# AD_605_Sheet1.net
KiCad netlist of a schematic drawn in Altium Designer
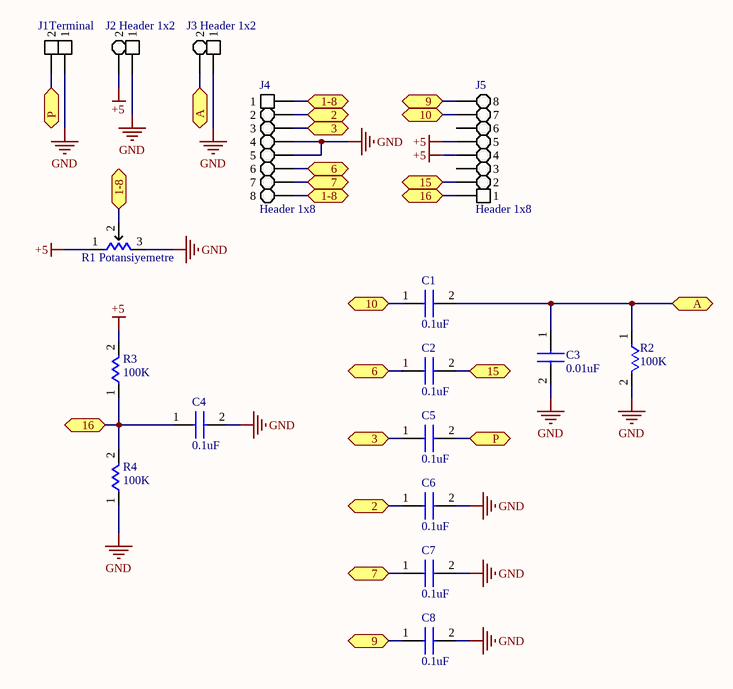
[diagram p0: AD_605_Sheet1.SchDoc]

(export (version "E")
  (design (tool "Eeschema 10.0.6"))
  (components
    (comp (ref "C1")
      (value "0.1uF")
      (footprint "CAP")
      (description "Capacitor")
      (libsource (lib "AD_605_Schlib1") (part "CAP"))
    )
    (comp (ref "C2")
      (value "0.1uF")
      (footprint "CAP")
      (description "Capacitor")
      (libsource (lib "AD_605_Schlib1") (part "CAP"))
    )
    (comp (ref "C3")
      (value "0.01uF")
      (footprint "CAP")
      (description "Capacitor")
      (libsource (lib "AD_605_Schlib1") (part "CAP"))
    )
    (comp (ref "C4")
      (value "0.1uF")
      (footprint "CAP")
      (description "Capacitor")
      (libsource (lib "AD_605_Schlib1") (part "CAP"))
    )
    (comp (ref "C5")
      (value "0.1uF")
      (footprint "CAP")
      (description "Capacitor")
      (libsource (lib "AD_605_Schlib1") (part "CAP"))
    )
    (comp (ref "C6")
      (value "0.1uF")
      (footprint "CAP")
      (description "Capacitor")
      (libsource (lib "AD_605_Schlib1") (part "CAP"))
    )
    (comp (ref "C7")
      (value "0.1uF")
      (footprint "CAP")
      (description "Capacitor")
      (libsource (lib "AD_605_Schlib1") (part "CAP"))
    )
    (comp (ref "C8")
      (value "0.1uF")
      (footprint "CAP")
      (description "Capacitor")
      (libsource (lib "AD_605_Schlib1") (part "CAP"))
    )
    (comp (ref "J1")
      (value "Terminal")
      (footprint "Terminal")
      (libsource (lib "AD_605_Schlib1") (part "Terminal"))
    )
    (comp (ref "J2")
      (value "Header 1x2")
      (footprint "Header 1x2")
      (description "Header")
      (libsource (lib "AD_605_Schlib1") (part "Header 1x2"))
    )
    (comp (ref "J3")
      (value "Header 1x2")
      (footprint "Header 1x2")
      (description "Header")
      (libsource (lib "AD_605_Schlib1") (part "Header 1x2"))
    )
    (comp (ref "J4")
      (value "Header 1x8")
      (footprint "Header 1x8")
      (description "Header")
      (libsource (lib "AD_605_Schlib1") (part "Header 1x8"))
    )
    (comp (ref "J5")
      (value "Header 1x8")
      (footprint "Header 1x8")
      (description "Header")
      (libsource (lib "AD_605_Schlib1") (part "Header 1x8"))
    )
    (comp (ref "R1")
      (value "Potansiyemetre")
      (footprint "Potansiyemetre")
      (libsource (lib "AD_605_Schlib1") (part "Potansiyemetre"))
    )
    (comp (ref "R2")
      (value "100K")
      (footprint "THT Res")
      (description "THT RES")
      (libsource (lib "AD_605_Schlib1") (part "THT RES"))
    )
    (comp (ref "R3")
      (value "100K")
      (footprint "THT Res")
      (description "THT RES")
      (libsource (lib "AD_605_Schlib1") (part "THT RES"))
    )
    (comp (ref "R4")
      (value "100K")
      (footprint "THT Res")
      (description "THT RES")
      (libsource (lib "AD_605_Schlib1") (part "THT RES"))
    )
  )
  (nets
    (net (code "1") (name "+5") (class "Default")
      (node (ref "J2") (pin "2") (pinfunction "2_2") (pintype "passive"))
      (node (ref "J5") (pin "4") (pinfunction "4_4") (pintype "passive"))
      (node (ref "J5") (pin "5") (pinfunction "5_5") (pintype "passive"))
      (node (ref "R1") (pin "1") (pinfunction "1_1") (pintype "passive"))
      (node (ref "R3") (pin "2") (pinfunction "2_2") (pintype "passive"))
    )
    (net (code "2") (name "/1-8") (class "Default")
      (node (ref "J4") (pin "1") (pinfunction "1_1") (pintype "passive"))
      (node (ref "J4") (pin "8") (pinfunction "8_8") (pintype "passive"))
      (node (ref "R1") (pin "2") (pinfunction "2_2") (pintype "passive"))
    )
    (net (code "3") (name "/2") (class "Default")
      (node (ref "C6") (pin "1") (pinfunction "1_1") (pintype "passive"))
      (node (ref "J4") (pin "2") (pinfunction "2_2") (pintype "passive"))
    )
    (net (code "4") (name "/3") (class "Default")
      (node (ref "C5") (pin "1") (pinfunction "1_1") (pintype "passive"))
      (node (ref "J4") (pin "3") (pinfunction "3_3") (pintype "passive"))
    )
    (net (code "5") (name "/6") (class "Default")
      (node (ref "C2") (pin "1") (pinfunction "1_1") (pintype "passive"))
      (node (ref "J4") (pin "6") (pinfunction "6_6") (pintype "passive"))
    )
    (net (code "6") (name "/7") (class "Default")
      (node (ref "C7") (pin "1") (pinfunction "1_1") (pintype "passive"))
      (node (ref "J4") (pin "7") (pinfunction "7_7") (pintype "passive"))
    )
    (net (code "7") (name "/9") (class "Default")
      (node (ref "C8") (pin "1") (pinfunction "1_1") (pintype "passive"))
      (node (ref "J5") (pin "8") (pinfunction "8_8") (pintype "passive"))
    )
    (net (code "8") (name "/10") (class "Default")
      (node (ref "C1") (pin "1") (pinfunction "1_1") (pintype "passive"))
      (node (ref "J5") (pin "7") (pinfunction "7_7") (pintype "passive"))
    )
    (net (code "9") (name "/15") (class "Default")
      (node (ref "C2") (pin "2") (pinfunction "2_2") (pintype "passive"))
      (node (ref "J5") (pin "2") (pinfunction "2_2") (pintype "passive"))
    )
    (net (code "10") (name "/16") (class "Default")
      (node (ref "C4") (pin "1") (pinfunction "1_1") (pintype "passive"))
      (node (ref "J5") (pin "1") (pinfunction "1_1") (pintype "passive"))
      (node (ref "R3") (pin "1") (pinfunction "1_1") (pintype "passive"))
      (node (ref "R4") (pin "2") (pinfunction "2_2") (pintype "passive"))
    )
    (net (code "11") (name "/A") (class "Default")
      (node (ref "C1") (pin "2") (pinfunction "2_2") (pintype "passive"))
      (node (ref "C3") (pin "1") (pinfunction "1_1") (pintype "passive"))
      (node (ref "J3") (pin "2") (pinfunction "2_2") (pintype "passive"))
      (node (ref "R2") (pin "1") (pinfunction "1_1") (pintype "passive"))
    )
    (net (code "12") (name "/P") (class "Default")
      (node (ref "C5") (pin "2") (pinfunction "2_2") (pintype "passive"))
      (node (ref "J1") (pin "2") (pinfunction "2_2") (pintype "passive"))
    )
    (net (code "13") (name "GND") (class "Default")
      (node (ref "C3") (pin "2") (pinfunction "2_2") (pintype "passive"))
      (node (ref "C4") (pin "2") (pinfunction "2_2") (pintype "passive"))
      (node (ref "C6") (pin "2") (pinfunction "2_2") (pintype "passive"))
      (node (ref "C7") (pin "2") (pinfunction "2_2") (pintype "passive"))
      (node (ref "C8") (pin "2") (pinfunction "2_2") (pintype "passive"))
      (node (ref "J1") (pin "1") (pinfunction "1_1") (pintype "passive"))
      (node (ref "J2") (pin "1") (pinfunction "1_1") (pintype "passive"))
      (node (ref "J3") (pin "1") (pinfunction "1_1") (pintype "passive"))
      (node (ref "J4") (pin "4") (pinfunction "4_4") (pintype "passive"))
      (node (ref "J4") (pin "5") (pinfunction "5_5") (pintype "passive"))
      (node (ref "R1") (pin "3") (pinfunction "3_3") (pintype "passive"))
      (node (ref "R2") (pin "2") (pinfunction "2_2") (pintype "passive"))
      (node (ref "R4") (pin "1") (pinfunction "1_1") (pintype "passive"))
    )
    (net (code "14") (name "unconnected-(J5-Pad3)") (class "Default")
      (node (ref "J5") (pin "3") (pinfunction "3_3") (pintype "passive"))
    )
    (net (code "15") (name "unconnected-(J5-Pad6)") (class "Default")
      (node (ref "J5") (pin "6") (pinfunction "6_6") (pintype "passive"))
    )
  )
)
